# IOTKit_ch_open_V2.net
KiCad netlist of a schematic drawn in EAGLE
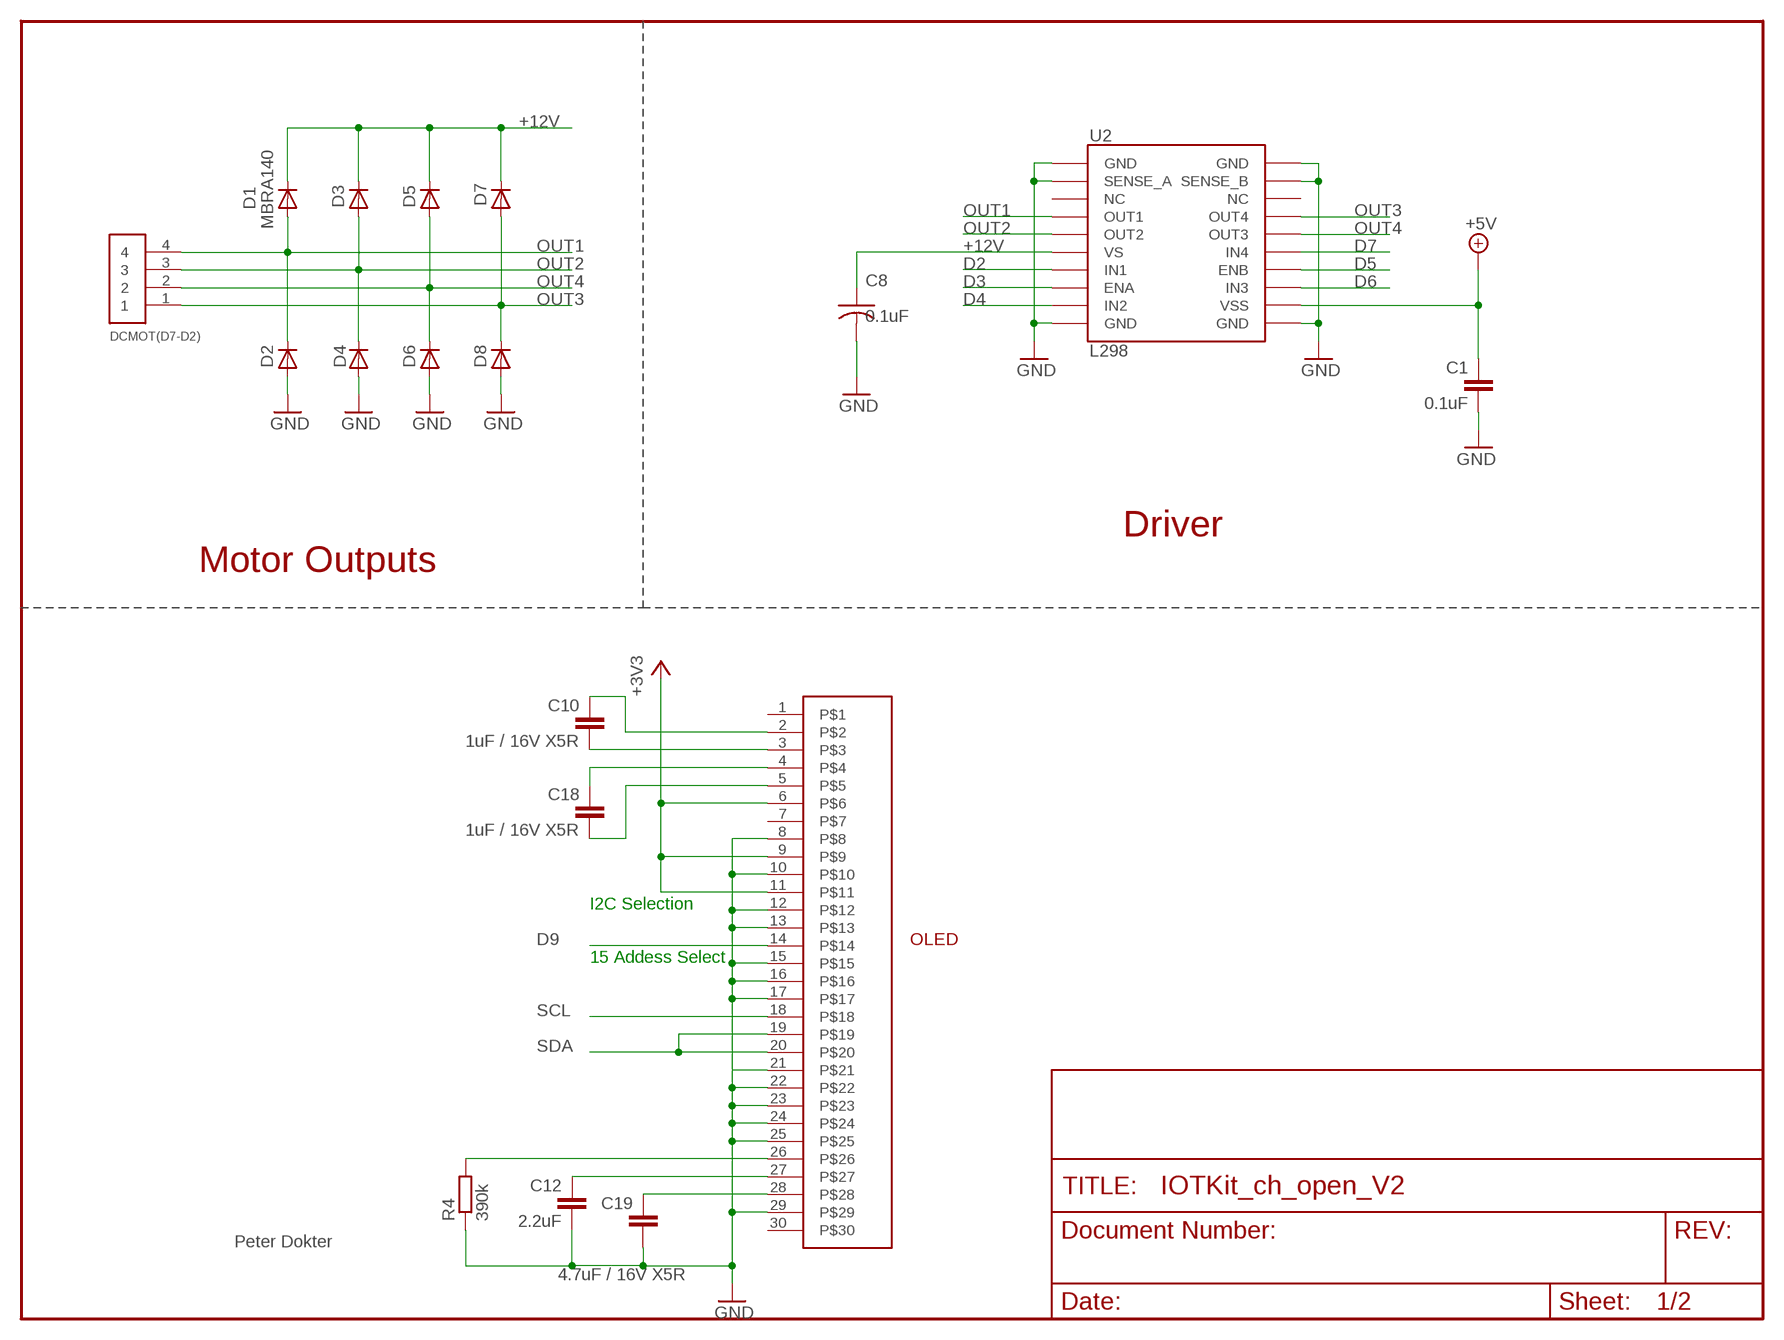
[diagram p0: schematic, sheet 1]
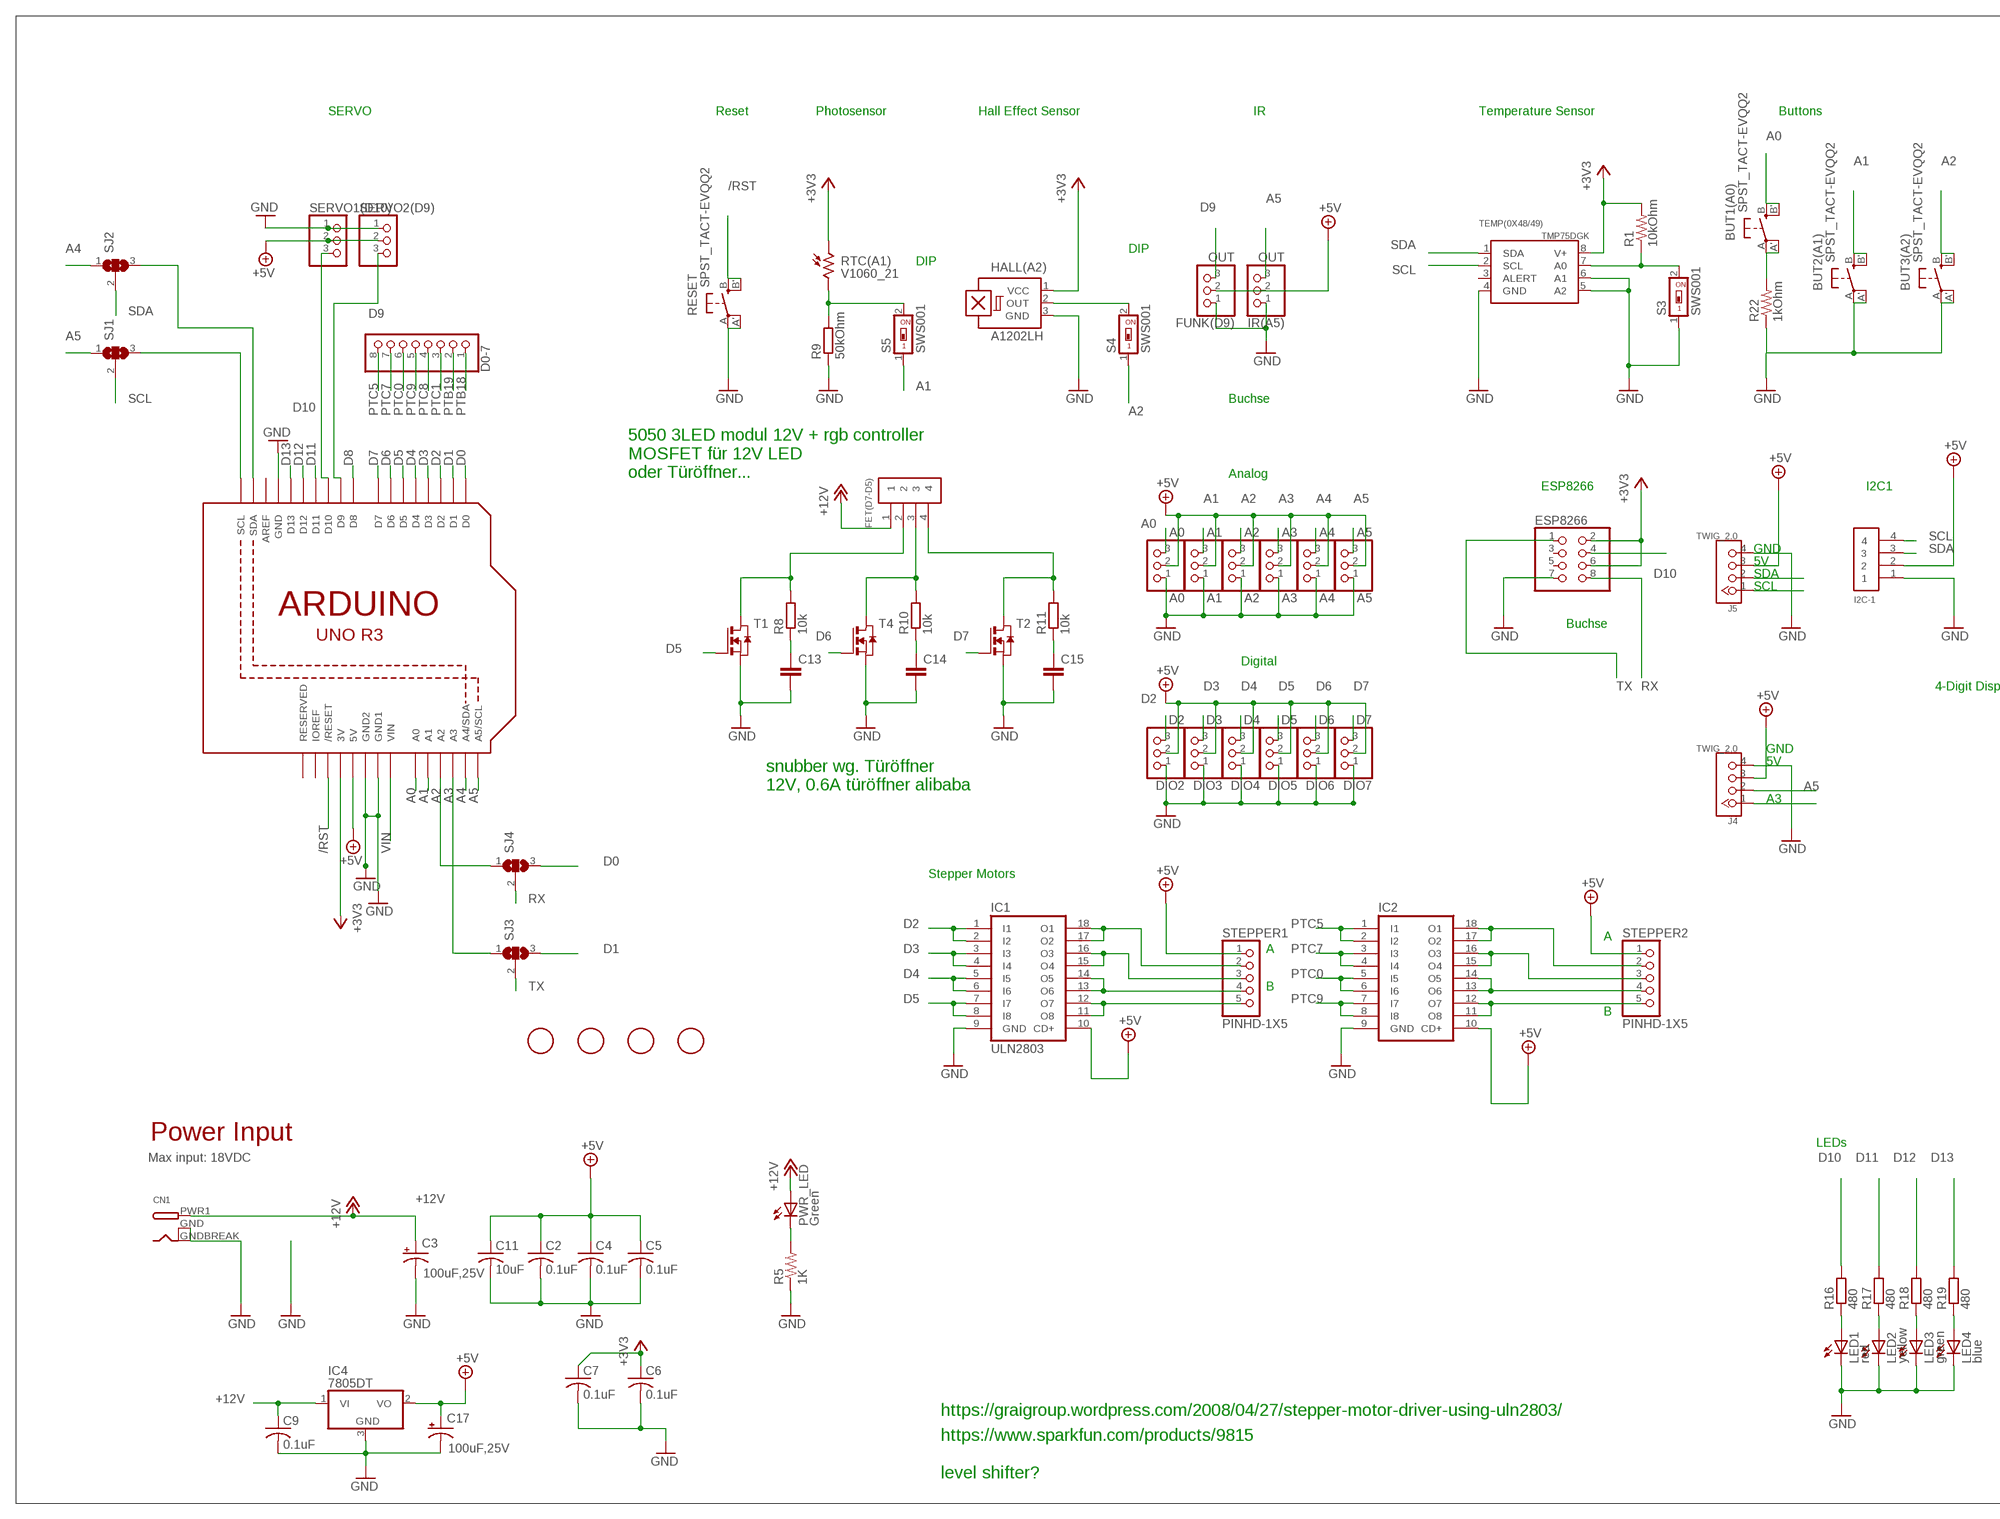
[diagram p1: schematic, sheet 2, part 1 of 2]
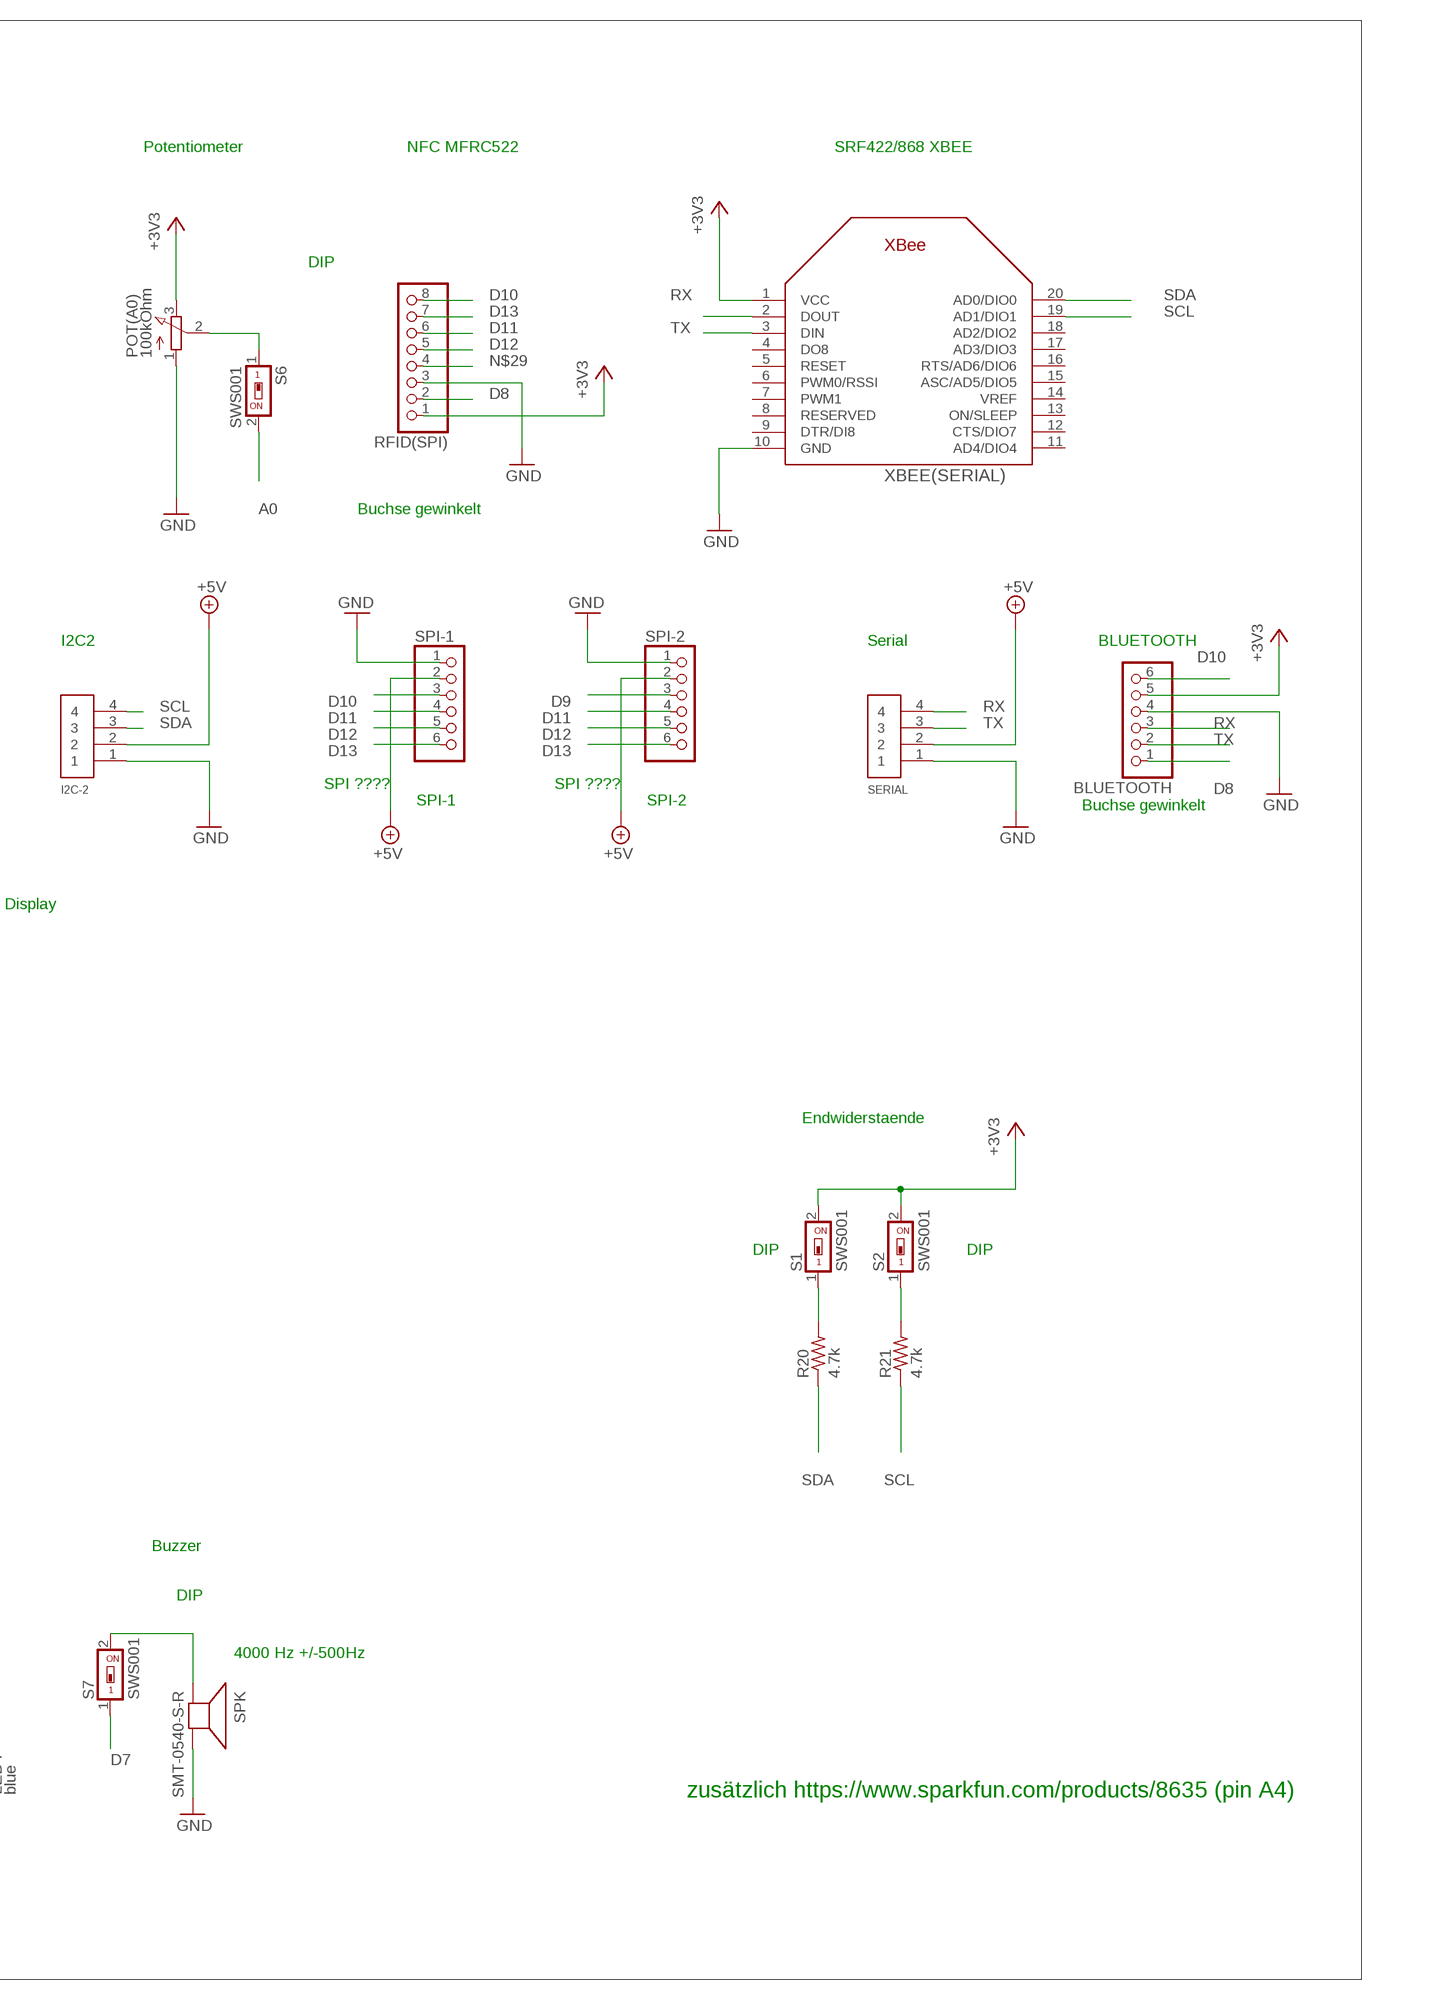
[diagram p2: schematic, sheet 2, part 2 of 2]

(export (version "E")
  (design (tool "Eeschema 10.0.6"))
  (components
    (comp (ref "A0")
      (value "A0")
      (footprint "eagle-import:1X03_LINE")
      (libsource (lib "eagle-import") (part "PINHD-1X3"))
    )
    (comp (ref "A1")
      (value "A1")
      (footprint "eagle-import:1X03_LINE")
      (libsource (lib "eagle-import") (part "PINHD-1X3"))
    )
    (comp (ref "A2")
      (value "A2")
      (footprint "eagle-import:1X03_LINE")
      (libsource (lib "eagle-import") (part "PINHD-1X3"))
    )
    (comp (ref "A3")
      (value "A3")
      (footprint "eagle-import:1X03_LINE")
      (libsource (lib "eagle-import") (part "PINHD-1X3"))
    )
    (comp (ref "A4")
      (value "A4")
      (footprint "eagle-import:1X03_LINE")
      (libsource (lib "eagle-import") (part "PINHD-1X3"))
    )
    (comp (ref "A5")
      (value "A5")
      (footprint "eagle-import:1X03_LINE")
      (libsource (lib "eagle-import") (part "PINHD-1X3"))
    )
    (comp (ref "BLUETOOTH")
      (value "PINHD-1X6B")
      (footprint "eagle-import:1X06-BIG")
      (libsource (lib "eagle-import") (part "PINHD-1X6B"))
    )
    (comp (ref "BUT1(A0)")
      (value "SPST_TACT-EVQQ2")
      (footprint "eagle-import:EVQ-Q2")
      (libsource (lib "eagle-import") (part "SPST_TACT-EVQQ2"))
    )
    (comp (ref "BUT2(A1)")
      (value "SPST_TACT-EVQQ2")
      (footprint "eagle-import:EVQ-Q2")
      (libsource (lib "eagle-import") (part "SPST_TACT-EVQQ2"))
    )
    (comp (ref "BUT3(A2)")
      (value "SPST_TACT-EVQQ2")
      (footprint "eagle-import:EVQ-Q2")
      (libsource (lib "eagle-import") (part "SPST_TACT-EVQQ2"))
    )
    (comp (ref "C2")
      (value "0.1uF")
      (footprint "eagle-import:C0603K")
      (libsource (lib "eagle-import") (part "C-USC0603K"))
    )
    (comp (ref "C3")
      (value "100uF,25V")
      (footprint "eagle-import:NIPPON_F80")
      (libsource (lib "eagle-import") (part "CAP_POLF80"))
    )
    (comp (ref "C4")
      (value "0.1uF")
      (footprint "eagle-import:C0603K")
      (libsource (lib "eagle-import") (part "C-USC0603K"))
    )
    (comp (ref "C5")
      (value "0.1uF")
      (footprint "eagle-import:C0603K")
      (libsource (lib "eagle-import") (part "C-USC0603K"))
    )
    (comp (ref "C6")
      (value "0.1uF")
      (footprint "eagle-import:C0603K")
      (libsource (lib "eagle-import") (part "C-USC0603K"))
    )
    (comp (ref "C7")
      (value "0.1uF")
      (footprint "eagle-import:C0603K")
      (libsource (lib "eagle-import") (part "C-USC0603K"))
    )
    (comp (ref "C9")
      (value "0.1uF")
      (footprint "eagle-import:C0805K")
      (libsource (lib "eagle-import") (part "C-USC0805K"))
    )
    (comp (ref "C11")
      (value "10uF")
      (footprint "eagle-import:C0805K")
      (libsource (lib "eagle-import") (part "C-USC0805K"))
    )
    (comp (ref "C13")
      (value "C-EUC0603")
      (footprint "eagle-import:C0603")
      (libsource (lib "eagle-import") (part "C-EUC0603"))
    )
    (comp (ref "C14")
      (value "C-EUC0603")
      (footprint "eagle-import:C0603")
      (libsource (lib "eagle-import") (part "C-EUC0603"))
    )
    (comp (ref "C15")
      (value "C-EUC0603")
      (footprint "eagle-import:C0603")
      (libsource (lib "eagle-import") (part "C-EUC0603"))
    )
    (comp (ref "C17")
      (value "100uF,25V")
      (footprint "eagle-import:NIPPON_F80")
      (libsource (lib "eagle-import") (part "CAP_POLF80"))
    )
    (comp (ref "CN1")
      (value "DCBARRELSMT")
      (footprint "eagle-import:DCJACK_2MM_SMT")
      (libsource (lib "eagle-import") (part "DCBARRELSMT"))
    )
    (comp (ref "D0-7")
      (value "PINHD-1X8CLEANBIG")
      (footprint "eagle-import:1X08-CLEANBIG")
      (libsource (lib "eagle-import") (part "PINHD-1X8CLEANBIG"))
    )
    (comp (ref "DIO2")
      (value "D2")
      (footprint "eagle-import:1X03_LINE")
      (libsource (lib "eagle-import") (part "PINHD-1X3"))
    )
    (comp (ref "DIO3")
      (value "D3")
      (footprint "eagle-import:1X03_LINE")
      (libsource (lib "eagle-import") (part "PINHD-1X3"))
    )
    (comp (ref "DIO4")
      (value "D4")
      (footprint "eagle-import:1X03_LINE")
      (libsource (lib "eagle-import") (part "PINHD-1X3"))
    )
    (comp (ref "DIO5")
      (value "D5")
      (footprint "eagle-import:1X03_LINE")
      (libsource (lib "eagle-import") (part "PINHD-1X3"))
    )
    (comp (ref "DIO6")
      (value "D6")
      (footprint "eagle-import:1X03_LINE")
      (libsource (lib "eagle-import") (part "PINHD-1X3"))
    )
    (comp (ref "DIO7")
      (value "D7")
      (footprint "eagle-import:1X03_LINE")
      (libsource (lib "eagle-import") (part "PINHD-1X3"))
    )
    (comp (ref "ESP8266")
      (value "PINHD-2X4")
      (footprint "eagle-import:2X04")
      (libsource (lib "eagle-import") (part "PINHD-2X4"))
    )
    (comp (ref "FET(D7-D5)")
      (value "1X4")
      (footprint "eagle-import:1X04_LINE")
      (libsource (lib "eagle-import") (part "1X4"))
    )
    (comp (ref "FUNK(D9)")
      (value "OUT")
      (footprint "eagle-import:1X03_LINE")
      (libsource (lib "eagle-import") (part "PINHD-1X3"))
    )
    (comp (ref "HALL(A2)")
      (value "A1202LH")
      (footprint "eagle-import:SOT23-W")
      (libsource (lib "eagle-import") (part "A12?LH02"))
    )
    (comp (ref "I2C-1")
      (value "1X4")
      (footprint "eagle-import:1X04_LINE")
      (libsource (lib "eagle-import") (part "1X4"))
    )
    (comp (ref "I2C-2")
      (value "1X4")
      (footprint "eagle-import:1X04_LINE")
      (libsource (lib "eagle-import") (part "1X4"))
    )
    (comp (ref "IC1")
      (value "ULN2803")
      (footprint "eagle-import:SO18W")
      (libsource (lib "eagle-import") (part "ULN2803ASO18W"))
    )
    (comp (ref "IC2")
      (value "ULN2803ASO18W")
      (footprint "eagle-import:SO18W")
      (libsource (lib "eagle-import") (part "ULN2803ASO18W"))
    )
    (comp (ref "IC4")
      (value "7805DT")
      (footprint "eagle-import:TO252")
      (libsource (lib "eagle-import") (part "78DT05"))
    )
    (comp (ref "IR(A5)")
      (value "OUT")
      (footprint "eagle-import:1X03_LINE")
      (libsource (lib "eagle-import") (part "PINHD-1X3"))
    )
    (comp (ref "J4")
      (value "TWIG_2.0")
      (footprint "eagle-import:2.0_1X4")
      (libsource (lib "eagle-import") (part "TWIG_2.0"))
    )
    (comp (ref "J5")
      (value "TWIG_2.0")
      (footprint "eagle-import:2.0_1X4")
      (libsource (lib "eagle-import") (part "TWIG_2.0"))
    )
    (comp (ref "LED1")
      (value "red")
      (footprint "eagle-import:CHIP-LED0603")
      (libsource (lib "eagle-import") (part "LEDCHIP-LED0603"))
    )
    (comp (ref "LED2")
      (value "yellow")
      (footprint "eagle-import:CHIP-LED0603")
      (libsource (lib "eagle-import") (part "LEDCHIP-LED0603"))
    )
    (comp (ref "LED3")
      (value "green")
      (footprint "eagle-import:CHIP-LED0603")
      (libsource (lib "eagle-import") (part "LEDCHIP-LED0603"))
    )
    (comp (ref "LED4")
      (value "blue")
      (footprint "eagle-import:CHIP-LED0603")
      (libsource (lib "eagle-import") (part "LEDCHIP-LED0603"))
    )
    (comp (ref "POT(A0)")
      (value "100kOhm")
      (footprint "eagle-import:EVUF")
      (libsource (lib "eagle-import") (part "EVUAF3"))
    )
    (comp (ref "PWR_LED")
      (value "Green")
      (footprint "eagle-import:CHIP-LED0805")
      (libsource (lib "eagle-import") (part "LEDCHIP-LED0805"))
    )
    (comp (ref "R1")
      (value "10kOhm")
      (footprint "eagle-import:R0805")
      (libsource (lib "eagle-import") (part "R-US_R0805"))
    )
    (comp (ref "R5")
      (value "1K")
      (footprint "eagle-import:R0805")
      (libsource (lib "eagle-import") (part "R-US_R0805"))
    )
    (comp (ref "R8")
      (value "10k")
      (footprint "eagle-import:R0805")
      (libsource (lib "eagle-import") (part "R-EU_R0805"))
    )
    (comp (ref "R9")
      (value "50kOhm")
      (footprint "eagle-import:R0603")
      (libsource (lib "eagle-import") (part "R-EU_R0603"))
    )
    (comp (ref "R10")
      (value "10k")
      (footprint "eagle-import:R0805")
      (libsource (lib "eagle-import") (part "R-EU_R0805"))
    )
    (comp (ref "R11")
      (value "10k")
      (footprint "eagle-import:R0805")
      (libsource (lib "eagle-import") (part "R-EU_R0805"))
    )
    (comp (ref "R16")
      (value "480")
      (footprint "eagle-import:R0603")
      (libsource (lib "eagle-import") (part "R-EU_R0603"))
    )
    (comp (ref "R17")
      (value "480")
      (footprint "eagle-import:R0603")
      (libsource (lib "eagle-import") (part "R-EU_R0603"))
    )
    (comp (ref "R18")
      (value "480")
      (footprint "eagle-import:R0603")
      (libsource (lib "eagle-import") (part "R-EU_R0603"))
    )
    (comp (ref "R19")
      (value "480")
      (footprint "eagle-import:R0603")
      (libsource (lib "eagle-import") (part "R-EU_R0603"))
    )
    (comp (ref "R20")
      (value "4.7k")
      (footprint "eagle-import:R0805")
      (libsource (lib "eagle-import") (part "R-US_R0805"))
    )
    (comp (ref "R21")
      (value "4.7k")
      (footprint "eagle-import:R0805")
      (libsource (lib "eagle-import") (part "R-US_R0805"))
    )
    (comp (ref "R22")
      (value "1kOhm")
      (footprint "eagle-import:R0805")
      (libsource (lib "eagle-import") (part "R-US_R0805"))
    )
    (comp (ref "RESET")
      (value "SPST_TACT-EVQQ2")
      (footprint "eagle-import:EVQ-Q2")
      (libsource (lib "eagle-import") (part "SPST_TACT-EVQQ2"))
    )
    (comp (ref "RFID(SPI)")
      (value "PINHD-1X8BIG")
      (footprint "eagle-import:1X08-BIG")
      (libsource (lib "eagle-import") (part "PINHD-1X8BIG"))
    )
    (comp (ref "RTC(A1)")
      (value "V1060_21")
      (footprint "eagle-import:TO-5_V10")
      (libsource (lib "eagle-import") (part "?1060V_21"))
    )
    (comp (ref "S1")
      (value "SWS001")
      (footprint "eagle-import:SMS-001")
      (libsource (lib "eagle-import") (part "SWS001"))
    )
    (comp (ref "S2")
      (value "SWS001")
      (footprint "eagle-import:SMS-001")
      (libsource (lib "eagle-import") (part "SWS001"))
    )
    (comp (ref "S3")
      (value "SWS001")
      (footprint "eagle-import:SMS-001")
      (libsource (lib "eagle-import") (part "SWS001"))
    )
    (comp (ref "S4")
      (value "SWS001")
      (footprint "eagle-import:SMS-001")
      (libsource (lib "eagle-import") (part "SWS001"))
    )
    (comp (ref "S5")
      (value "SWS001")
      (footprint "eagle-import:SMS-001")
      (libsource (lib "eagle-import") (part "SWS001"))
    )
    (comp (ref "S6")
      (value "SWS001")
      (footprint "eagle-import:SMS-001")
      (libsource (lib "eagle-import") (part "SWS001"))
    )
    (comp (ref "S7")
      (value "SWS001")
      (footprint "eagle-import:SMS-001")
      (libsource (lib "eagle-import") (part "SWS001"))
    )
    (comp (ref "SERIAL")
      (value "1X4")
      (footprint "eagle-import:1X04_LINE")
      (libsource (lib "eagle-import") (part "1X4"))
    )
    (comp (ref "SERVO1(D10)")
      (value "PINHD-1X3")
      (footprint "eagle-import:1X03")
      (libsource (lib "eagle-import") (part "adafruit_PINHD-1X3"))
    )
    (comp (ref "SERVO2(D9)")
      (value "PINHD-1X3")
      (footprint "eagle-import:1X03")
      (libsource (lib "eagle-import") (part "adafruit_PINHD-1X3"))
    )
    (comp (ref "SJ1")
      (value "SJ2W")
      (footprint "eagle-import:SJ_2")
      (libsource (lib "eagle-import") (part "SJ2W"))
    )
    (comp (ref "SJ2")
      (value "SJ2W")
      (footprint "eagle-import:SJ_2")
      (libsource (lib "eagle-import") (part "SJ2W"))
    )
    (comp (ref "SJ3")
      (value "SJ2W")
      (footprint "eagle-import:SJ_2")
      (libsource (lib "eagle-import") (part "SJ2W"))
    )
    (comp (ref "SJ4")
      (value "SJ2W")
      (footprint "eagle-import:SJ_2")
      (libsource (lib "eagle-import") (part "SJ2W"))
    )
    (comp (ref "SPI-1")
      (value "PINHD-1X6B")
      (footprint "eagle-import:1X06-BIG")
      (libsource (lib "eagle-import") (part "PINHD-1X6B"))
    )
    (comp (ref "SPI-2")
      (value "PINHD-1X6B")
      (footprint "eagle-import:1X06-BIG")
      (libsource (lib "eagle-import") (part "PINHD-1X6B"))
    )
    (comp (ref "SPK")
      (value "SMT-0540-S-R")
      (footprint "eagle-import:SMT-0540-S-R")
      (libsource (lib "eagle-import") (part "SMT-0540-S-R"))
    )
    (comp (ref "STEPPER1")
      (value "PINHD-1X5")
      (footprint "eagle-import:1X05")
      (libsource (lib "eagle-import") (part "PINHD-1X5"))
    )
    (comp (ref "STEPPER2")
      (value "PINHD-1X5")
      (footprint "eagle-import:1X05")
      (libsource (lib "eagle-import") (part "PINHD-1X5"))
    )
    (comp (ref "T1")
      (value "NMOSSOT223")
      (footprint "eagle-import:SOT223")
      (libsource (lib "eagle-import") (part "NMOSSOT223"))
    )
    (comp (ref "T2")
      (value "NMOSSOT223")
      (footprint "eagle-import:SOT223")
      (libsource (lib "eagle-import") (part "NMOSSOT223"))
    )
    (comp (ref "T4")
      (value "NMOSSOT223")
      (footprint "eagle-import:SOT223")
      (libsource (lib "eagle-import") (part "NMOSSOT223"))
    )
    (comp (ref "TEMP(0X48/49)")
      (value "TMP75DGK")
      (footprint "eagle-import:MSOP8")
      (libsource (lib "eagle-import") (part "TMP75DGK"))
    )
    (comp (ref "U$1")
      (value "FIDUCIAL")
      (footprint "eagle-import:FIDUCIAL_1MM")
      (libsource (lib "eagle-import") (part "FIDUCIAL"))
    )
    (comp (ref "U$2")
      (value "FIDUCIAL")
      (footprint "eagle-import:FIDUCIAL_1MM")
      (libsource (lib "eagle-import") (part "FIDUCIAL"))
    )
    (comp (ref "U$3")
      (value "FIDUCIAL")
      (footprint "eagle-import:FIDUCIAL_1MM")
      (libsource (lib "eagle-import") (part "FIDUCIAL"))
    )
    (comp (ref "U$5")
      (value "ARDUINOR3NONAME")
      (footprint "eagle-import:ARDUINOR2_ICSP_NODIM_NONAME")
      (libsource (lib "eagle-import") (part "ARDUINOR3NONAME"))
    )
    (comp (ref "U$6")
      (value "FIDUCIAL")
      (footprint "eagle-import:FIDUCIAL_1MM")
      (libsource (lib "eagle-import") (part "FIDUCIAL"))
    )
    (comp (ref "XBEE(SERIAL)")
      (value "XBEE")
      (footprint "eagle-import:XBEE")
      (libsource (lib "eagle-import") (part "XBEE"))
    )
    (comp (ref "C1")
      (value "0.1uF")
      (footprint "eagle-import:0402-CAP")
      (libsource (lib "eagle-import") (part "CAP0402-CAP"))
    )
    (comp (ref "C8")
      (value "0.1uF")
      (footprint "eagle-import:C0603K")
      (libsource (lib "eagle-import") (part "C-USC0603K"))
    )
    (comp (ref "C10")
      (value "1uF / 16V X5R")
      (footprint "eagle-import:0603-CAP")
      (libsource (lib "eagle-import") (part "CAP0603-CAP"))
    )
    (comp (ref "C12")
      (value "2.2uF")
      (footprint "eagle-import:0603-CAP")
      (libsource (lib "eagle-import") (part "CAP0603-CAP"))
    )
    (comp (ref "C18")
      (value "1uF / 16V X5R")
      (footprint "eagle-import:0603-CAP")
      (libsource (lib "eagle-import") (part "CAP0603-CAP"))
    )
    (comp (ref "C19")
      (value "4.7uF / 16V X5R")
      (footprint "eagle-import:0603-CAP")
      (libsource (lib "eagle-import") (part "CAP0603-CAP"))
    )
    (comp (ref "D1")
      (value "MBRA140")
      (footprint "eagle-import:SMA-DIODE")
      (libsource (lib "eagle-import") (part "DIODESMA"))
    )
    (comp (ref "D2")
      (value "MBRA140")
      (footprint "eagle-import:SMA-DIODE")
      (libsource (lib "eagle-import") (part "DIODESMA"))
    )
    (comp (ref "D3")
      (value "MBRA140")
      (footprint "eagle-import:SMA-DIODE")
      (libsource (lib "eagle-import") (part "DIODESMA"))
    )
    (comp (ref "D4")
      (value "MBRA140")
      (footprint "eagle-import:SMA-DIODE")
      (libsource (lib "eagle-import") (part "DIODESMA"))
    )
    (comp (ref "D5")
      (value "MBRA140")
      (footprint "eagle-import:SMA-DIODE")
      (libsource (lib "eagle-import") (part "DIODESMA"))
    )
    (comp (ref "D6")
      (value "MBRA140")
      (footprint "eagle-import:SMA-DIODE")
      (libsource (lib "eagle-import") (part "DIODESMA"))
    )
    (comp (ref "D7")
      (value "MBRA140")
      (footprint "eagle-import:SMA-DIODE")
      (libsource (lib "eagle-import") (part "DIODESMA"))
    )
    (comp (ref "D8")
      (value "MBRA140")
      (footprint "eagle-import:SMA-DIODE")
      (libsource (lib "eagle-import") (part "DIODESMA"))
    )
    (comp (ref "DCMOT(D7-D2)")
      (value "1X4")
      (footprint "eagle-import:1X04_LINE")
      (libsource (lib "eagle-import") (part "1X4"))
    )
    (comp (ref "R4")
      (value "390k")
      (footprint "eagle-import:R0603")
      (libsource (lib "eagle-import") (part "R-EU_R0603"))
    )
    (comp (ref "U$4")
      (value "OLED_096_1")
      (footprint "eagle-import:OLED_096_1")
      (libsource (lib "eagle-import") (part "OLED_096_1"))
    )
    (comp (ref "U2")
      (value "L298")
      (footprint "eagle-import:POWERSO20")
      (libsource (lib "eagle-import") (part "L298_BRIDGE_DRIVER"))
    )
  )
  (nets
    (net (code "1") (name "+3V3") (class "Default")
      (node (ref "BLUETOOTH") (pin "5") (pinfunction "5_5") (pintype "passive"))
      (node (ref "C6") (pin "1") (pinfunction "1_1") (pintype "passive"))
      (node (ref "C7") (pin "1") (pinfunction "1_1") (pintype "passive"))
      (node (ref "ESP8266") (pin "2") (pinfunction "2_2") (pintype "passive"))
      (node (ref "ESP8266") (pin "6") (pinfunction "6_6") (pintype "passive"))
      (node (ref "HALL(A2)") (pin "1") (pinfunction "VCC_1") (pintype "power_in"))
      (node (ref "POT(A0)") (pin "3") (pinfunction "E_3") (pintype "passive"))
      (node (ref "R1") (pin "2") (pinfunction "2_2") (pintype "passive"))
      (node (ref "RFID(SPI)") (pin "1") (pinfunction "1_1") (pintype "passive"))
      (node (ref "RTC(A1)") (pin "1") (pinfunction "1_1") (pintype "passive"))
      (node (ref "S1") (pin "2") (pinfunction "2_2") (pintype "passive"))
      (node (ref "S2") (pin "2") (pinfunction "2_2") (pintype "passive"))
      (node (ref "TEMP(0X48/49)") (pin "8") (pinfunction "V+_8") (pintype "bidirectional"))
      (node (ref "U$4") (pin "11") (pinfunction "P$11_11") (pintype "bidirectional"))
      (node (ref "U$4") (pin "6") (pinfunction "P$6_6") (pintype "bidirectional"))
      (node (ref "U$4") (pin "9") (pinfunction "P$9_9") (pintype "bidirectional"))
      (node (ref "U$5") (pin "3V") (pinfunction "3V_3V") (pintype "power_in"))
      (node (ref "XBEE(SERIAL)") (pin "1") (pinfunction "VCC_1") (pintype "power_in"))
    )
    (net (code "2") (name "+5V") (class "Default")
      (node (ref "A0") (pin "2") (pinfunction "2_2") (pintype "passive"))
      (node (ref "A1") (pin "2") (pinfunction "2_2") (pintype "passive"))
      (node (ref "A2") (pin "2") (pinfunction "2_2") (pintype "passive"))
      (node (ref "A3") (pin "2") (pinfunction "2_2") (pintype "passive"))
      (node (ref "A4") (pin "2") (pinfunction "2_2") (pintype "passive"))
      (node (ref "A5") (pin "2") (pinfunction "2_2") (pintype "passive"))
      (node (ref "C1") (pin "1") (pinfunction "1_1") (pintype "passive"))
      (node (ref "C11") (pin "1") (pinfunction "1_1") (pintype "passive"))
      (node (ref "C17") (pin "+") (pinfunction "+_+") (pintype "passive"))
      (node (ref "C2") (pin "1") (pinfunction "1_1") (pintype "passive"))
      (node (ref "C4") (pin "1") (pinfunction "1_1") (pintype "passive"))
      (node (ref "C5") (pin "1") (pinfunction "1_1") (pintype "passive"))
      (node (ref "DIO2") (pin "2") (pinfunction "2_2") (pintype "passive"))
      (node (ref "DIO3") (pin "2") (pinfunction "2_2") (pintype "passive"))
      (node (ref "DIO4") (pin "2") (pinfunction "2_2") (pintype "passive"))
      (node (ref "DIO5") (pin "2") (pinfunction "2_2") (pintype "passive"))
      (node (ref "DIO6") (pin "2") (pinfunction "2_2") (pintype "passive"))
      (node (ref "DIO7") (pin "2") (pinfunction "2_2") (pintype "passive"))
      (node (ref "FUNK(D9)") (pin "2") (pinfunction "2_2") (pintype "passive"))
      (node (ref "I2C-1") (pin "2") (pinfunction "2_2") (pintype "bidirectional"))
      (node (ref "I2C-2") (pin "2") (pinfunction "2_2") (pintype "bidirectional"))
      (node (ref "IC1") (pin "10") (pinfunction "CD+_10") (pintype "passive"))
      (node (ref "IC2") (pin "10") (pinfunction "CD+_10") (pintype "passive"))
      (node (ref "IC4") (pin "2") (pinfunction "VO_2") (pintype "passive"))
      (node (ref "IR(A5)") (pin "2") (pinfunction "2_2") (pintype "passive"))
      (node (ref "J4") (pin "3") (pinfunction "3_3") (pintype "bidirectional"))
      (node (ref "J5") (pin "3") (pinfunction "3_3") (pintype "bidirectional"))
      (node (ref "SERIAL") (pin "2") (pinfunction "2_2") (pintype "bidirectional"))
      (node (ref "SERVO1(D10)") (pin "2") (pinfunction "2_2") (pintype "passive"))
      (node (ref "SERVO2(D9)") (pin "2") (pinfunction "2_2") (pintype "passive"))
      (node (ref "SPI-1") (pin "2") (pinfunction "2_2") (pintype "passive"))
      (node (ref "SPI-2") (pin "2") (pinfunction "2_2") (pintype "passive"))
      (node (ref "STEPPER1") (pin "1") (pinfunction "1_1") (pintype "passive"))
      (node (ref "STEPPER2") (pin "1") (pinfunction "1_1") (pintype "passive"))
      (node (ref "U$5") (pin "5V") (pinfunction "5V_5V") (pintype "power_in"))
      (node (ref "U2") (pin "P$12") (pinfunction "VSS_P$12") (pintype "bidirectional"))
    )
    (net (code "3") (name "+12V") (class "Default")
      (node (ref "C3") (pin "+") (pinfunction "+_+") (pintype "passive"))
      (node (ref "C8") (pin "1") (pinfunction "1_1") (pintype "passive"))
      (node (ref "C9") (pin "1") (pinfunction "1_1") (pintype "passive"))
      (node (ref "CN1") (pin "PWR1") (pinfunction "PWR_PWR1") (pintype "power_in"))
      (node (ref "D1") (pin "C") (pinfunction "C_C") (pintype "passive"))
      (node (ref "D3") (pin "C") (pinfunction "C_C") (pintype "passive"))
      (node (ref "D5") (pin "C") (pinfunction "C_C") (pintype "passive"))
      (node (ref "D7") (pin "C") (pinfunction "C_C") (pintype "passive"))
      (node (ref "FET(D7-D5)") (pin "1") (pinfunction "1_1") (pintype "bidirectional"))
      (node (ref "IC4") (pin "1") (pinfunction "VI_1") (pintype "input"))
      (node (ref "PWR_LED") (pin "A") (pinfunction "A_A") (pintype "passive"))
      (node (ref "U2") (pin "P$6") (pinfunction "VS_P$6") (pintype "bidirectional"))
    )
    (net (code "4") (name "A0") (class "Default")
      (node (ref "A0") (pin "3") (pinfunction "3_3") (pintype "passive"))
      (node (ref "BUT1(A0)") (pin "B") (pinfunction "S_B") (pintype "passive"))
      (node (ref "BUT1(A0)") (pin "B'") (pinfunction "S1_B'") (pintype "passive"))
      (node (ref "S6") (pin "2") (pinfunction "2_2") (pintype "passive"))
      (node (ref "U$5") (pin "A0") (pinfunction "A0_A0") (pintype "bidirectional"))
    )
    (net (code "5") (name "A1") (class "Default")
      (node (ref "A1") (pin "3") (pinfunction "3_3") (pintype "passive"))
      (node (ref "BUT2(A1)") (pin "B") (pinfunction "S_B") (pintype "passive"))
      (node (ref "BUT2(A1)") (pin "B'") (pinfunction "S1_B'") (pintype "passive"))
      (node (ref "S5") (pin "1") (pinfunction "1_1") (pintype "passive"))
      (node (ref "U$5") (pin "A1") (pinfunction "A1_A1") (pintype "bidirectional"))
    )
    (net (code "6") (name "A2") (class "Default")
      (node (ref "A2") (pin "3") (pinfunction "3_3") (pintype "passive"))
      (node (ref "BUT3(A2)") (pin "B") (pinfunction "S_B") (pintype "passive"))
      (node (ref "BUT3(A2)") (pin "B'") (pinfunction "S1_B'") (pintype "passive"))
      (node (ref "S4") (pin "1") (pinfunction "1_1") (pintype "passive"))
      (node (ref "SJ4") (pin "1") (pinfunction "1_1") (pintype "passive"))
      (node (ref "U$5") (pin "A2") (pinfunction "A2_A2") (pintype "bidirectional"))
    )
    (net (code "7") (name "A3") (class "Default")
      (node (ref "A3") (pin "3") (pinfunction "3_3") (pintype "passive"))
      (node (ref "J4") (pin "1") (pinfunction "1_1") (pintype "bidirectional"))
      (node (ref "SJ3") (pin "1") (pinfunction "1_1") (pintype "passive"))
      (node (ref "U$5") (pin "A3") (pinfunction "A3_A3") (pintype "bidirectional"))
    )
    (net (code "8") (name "A4") (class "Default")
      (node (ref "A4") (pin "3") (pinfunction "3_3") (pintype "passive"))
      (node (ref "SJ2") (pin "1") (pinfunction "1_1") (pintype "passive"))
      (node (ref "U$5") (pin "A4") (pinfunction "A4/SDA_A4") (pintype "bidirectional"))
    )
    (net (code "9") (name "A5") (class "Default")
      (node (ref "A5") (pin "3") (pinfunction "3_3") (pintype "passive"))
      (node (ref "IR(A5)") (pin "3") (pinfunction "3_3") (pintype "passive"))
      (node (ref "J4") (pin "2") (pinfunction "2_2") (pintype "bidirectional"))
      (node (ref "SJ1") (pin "1") (pinfunction "1_1") (pintype "passive"))
      (node (ref "U$5") (pin "A5") (pinfunction "A5/SCL_A5") (pintype "bidirectional"))
    )
    (net (code "10") (name "D0") (class "Default")
      (node (ref "SJ4") (pin "3") (pinfunction "3_3") (pintype "passive"))
      (node (ref "U$5") (pin "D0") (pinfunction "D0_D0") (pintype "bidirectional"))
    )
    (net (code "11") (name "D1") (class "Default")
      (node (ref "SJ3") (pin "3") (pinfunction "3_3") (pintype "passive"))
      (node (ref "U$5") (pin "D1") (pinfunction "D1_D1") (pintype "bidirectional"))
    )
    (net (code "12") (name "D2") (class "Default")
      (node (ref "DIO2") (pin "3") (pinfunction "3_3") (pintype "passive"))
      (node (ref "IC1") (pin "1") (pinfunction "I1_1") (pintype "input"))
      (node (ref "IC1") (pin "2") (pinfunction "I2_2") (pintype "input"))
      (node (ref "U$5") (pin "D2") (pinfunction "D2_D2") (pintype "bidirectional"))
      (node (ref "U2") (pin "P$7") (pinfunction "IN1_P$7") (pintype "bidirectional"))
    )
    (net (code "13") (name "D3") (class "Default")
      (node (ref "DIO3") (pin "3") (pinfunction "3_3") (pintype "passive"))
      (node (ref "IC1") (pin "3") (pinfunction "I3_3") (pintype "input"))
      (node (ref "IC1") (pin "4") (pinfunction "I4_4") (pintype "input"))
      (node (ref "U$5") (pin "D3") (pinfunction "D3_D3") (pintype "bidirectional"))
      (node (ref "U2") (pin "P$8") (pinfunction "ENA_P$8") (pintype "bidirectional"))
    )
    (net (code "14") (name "D4") (class "Default")
      (node (ref "DIO4") (pin "3") (pinfunction "3_3") (pintype "passive"))
      (node (ref "IC1") (pin "5") (pinfunction "I5_5") (pintype "input"))
      (node (ref "IC1") (pin "6") (pinfunction "I6_6") (pintype "input"))
      (node (ref "U$5") (pin "D4") (pinfunction "D4_D4") (pintype "bidirectional"))
      (node (ref "U2") (pin "P$9") (pinfunction "IN2_P$9") (pintype "bidirectional"))
    )
    (net (code "15") (name "D5") (class "Default")
      (node (ref "DIO5") (pin "3") (pinfunction "3_3") (pintype "passive"))
      (node (ref "IC1") (pin "7") (pinfunction "I7_7") (pintype "input"))
      (node (ref "IC1") (pin "8") (pinfunction "I8_8") (pintype "input"))
      (node (ref "T1") (pin "1") (pinfunction "G_1") (pintype "passive"))
      (node (ref "U$5") (pin "D5") (pinfunction "D5_D5") (pintype "bidirectional"))
      (node (ref "U2") (pin "P$14") (pinfunction "ENB_P$14") (pintype "bidirectional"))
    )
    (net (code "16") (name "D6") (class "Default")
      (node (ref "DIO6") (pin "3") (pinfunction "3_3") (pintype "passive"))
      (node (ref "T4") (pin "1") (pinfunction "G_1") (pintype "passive"))
      (node (ref "U$5") (pin "D6") (pinfunction "D6_D6") (pintype "bidirectional"))
      (node (ref "U2") (pin "P$13") (pinfunction "IN3_P$13") (pintype "bidirectional"))
    )
    (net (code "17") (name "D7") (class "Default")
      (node (ref "DIO7") (pin "3") (pinfunction "3_3") (pintype "passive"))
      (node (ref "S7") (pin "1") (pinfunction "1_1") (pintype "passive"))
      (node (ref "T2") (pin "1") (pinfunction "G_1") (pintype "passive"))
      (node (ref "U$5") (pin "D7") (pinfunction "D7_D7") (pintype "bidirectional"))
      (node (ref "U2") (pin "P$15") (pinfunction "IN4_P$15") (pintype "bidirectional"))
    )
    (net (code "18") (name "D8") (class "Default")
      (node (ref "BLUETOOTH") (pin "1") (pinfunction "1_1") (pintype "passive"))
      (node (ref "RFID(SPI)") (pin "2") (pinfunction "2_2") (pintype "passive"))
      (node (ref "U$5") (pin "D8") (pinfunction "D8_D8") (pintype "bidirectional"))
    )
    (net (code "19") (name "D9") (class "Default")
      (node (ref "FUNK(D9)") (pin "3") (pinfunction "3_3") (pintype "passive"))
      (node (ref "SERVO2(D9)") (pin "3") (pinfunction "3_3") (pintype "passive"))
      (node (ref "SPI-2") (pin "3") (pinfunction "3_3") (pintype "passive"))
      (node (ref "U$4") (pin "14") (pinfunction "P$14_14") (pintype "bidirectional"))
      (node (ref "U$5") (pin "D9") (pinfunction "D9_D9") (pintype "bidirectional"))
    )
    (net (code "20") (name "D10") (class "Default")
      (node (ref "BLUETOOTH") (pin "6") (pinfunction "6_6") (pintype "passive"))
      (node (ref "ESP8266") (pin "4") (pinfunction "4_4") (pintype "passive"))
      (node (ref "R16") (pin "2") (pinfunction "2_2") (pintype "passive"))
      (node (ref "RFID(SPI)") (pin "8") (pinfunction "8_8") (pintype "passive"))
      (node (ref "SERVO1(D10)") (pin "3") (pinfunction "3_3") (pintype "passive"))
      (node (ref "SPI-1") (pin "3") (pinfunction "3_3") (pintype "passive"))
      (node (ref "U$5") (pin "D10") (pinfunction "D10_D10") (pintype "bidirectional"))
    )
    (net (code "21") (name "D11") (class "Default")
      (node (ref "R17") (pin "2") (pinfunction "2_2") (pintype "passive"))
      (node (ref "RFID(SPI)") (pin "6") (pinfunction "6_6") (pintype "passive"))
      (node (ref "SPI-1") (pin "4") (pinfunction "4_4") (pintype "passive"))
      (node (ref "SPI-2") (pin "4") (pinfunction "4_4") (pintype "passive"))
      (node (ref "U$5") (pin "D11") (pinfunction "D11_D11") (pintype "bidirectional"))
    )
    (net (code "22") (name "D12") (class "Default")
      (node (ref "R18") (pin "2") (pinfunction "2_2") (pintype "passive"))
      (node (ref "RFID(SPI)") (pin "5") (pinfunction "5_5") (pintype "passive"))
      (node (ref "SPI-1") (pin "5") (pinfunction "5_5") (pintype "passive"))
      (node (ref "SPI-2") (pin "5") (pinfunction "5_5") (pintype "passive"))
      (node (ref "U$5") (pin "D12") (pinfunction "D12_D12") (pintype "bidirectional"))
    )
    (net (code "23") (name "D13") (class "Default")
      (node (ref "R19") (pin "2") (pinfunction "2_2") (pintype "passive"))
      (node (ref "RFID(SPI)") (pin "7") (pinfunction "7_7") (pintype "passive"))
      (node (ref "SPI-1") (pin "6") (pinfunction "6_6") (pintype "passive"))
      (node (ref "SPI-2") (pin "6") (pinfunction "6_6") (pintype "passive"))
      (node (ref "U$5") (pin "D13") (pinfunction "D13_D13") (pintype "bidirectional"))
    )
    (net (code "24") (name "GND") (class "Default")
      (node (ref "A0") (pin "1") (pinfunction "1_1") (pintype "passive"))
      (node (ref "A1") (pin "1") (pinfunction "1_1") (pintype "passive"))
      (node (ref "A2") (pin "1") (pinfunction "1_1") (pintype "passive"))
      (node (ref "A3") (pin "1") (pinfunction "1_1") (pintype "passive"))
      (node (ref "A4") (pin "1") (pinfunction "1_1") (pintype "passive"))
      (node (ref "A5") (pin "1") (pinfunction "1_1") (pintype "passive"))
      (node (ref "BLUETOOTH") (pin "4") (pinfunction "4_4") (pintype "passive"))
      (node (ref "BUT2(A1)") (pin "A") (pinfunction "P_A") (pintype "passive"))
      (node (ref "BUT2(A1)") (pin "A'") (pinfunction "P1_A'") (pintype "passive"))
      (node (ref "BUT3(A2)") (pin "A") (pinfunction "P_A") (pintype "passive"))
      (node (ref "BUT3(A2)") (pin "A'") (pinfunction "P1_A'") (pintype "passive"))
      (node (ref "C1") (pin "2") (pinfunction "2_2") (pintype "passive"))
      (node (ref "C11") (pin "2") (pinfunction "2_2") (pintype "passive"))
      (node (ref "C12") (pin "2") (pinfunction "2_2") (pintype "passive"))
      (node (ref "C13") (pin "2") (pinfunction "2_2") (pintype "passive"))
      (node (ref "C14") (pin "2") (pinfunction "2_2") (pintype "passive"))
      (node (ref "C15") (pin "2") (pinfunction "2_2") (pintype "passive"))
      (node (ref "C17") (pin "-") (pinfunction "-_-") (pintype "passive"))
      (node (ref "C19") (pin "2") (pinfunction "2_2") (pintype "passive"))
      (node (ref "C2") (pin "2") (pinfunction "2_2") (pintype "passive"))
      (node (ref "C3") (pin "-") (pinfunction "-_-") (pintype "passive"))
      (node (ref "C4") (pin "2") (pinfunction "2_2") (pintype "passive"))
      (node (ref "C5") (pin "2") (pinfunction "2_2") (pintype "passive"))
      (node (ref "C6") (pin "2") (pinfunction "2_2") (pintype "passive"))
      (node (ref "C7") (pin "2") (pinfunction "2_2") (pintype "passive"))
      (node (ref "C8") (pin "2") (pinfunction "2_2") (pintype "passive"))
      (node (ref "C9") (pin "2") (pinfunction "2_2") (pintype "passive"))
      (node (ref "CN1") (pin "GND") (pinfunction "GNDBREAK_GND") (pintype "power_in"))
      (node (ref "CN1") (pin "GNDBREAK") (pinfunction "GND_GNDBREAK") (pintype "power_in"))
      (node (ref "D2") (pin "A") (pinfunction "A_A") (pintype "passive"))
      (node (ref "D4") (pin "A") (pinfunction "A_A") (pintype "passive"))
      (node (ref "D6") (pin "A") (pinfunction "A_A") (pintype "passive"))
      (node (ref "D8") (pin "A") (pinfunction "A_A") (pintype "passive"))
      (node (ref "DIO2") (pin "1") (pinfunction "1_1") (pintype "passive"))
      (node (ref "DIO3") (pin "1") (pinfunction "1_1") (pintype "passive"))
      (node (ref "DIO4") (pin "1") (pinfunction "1_1") (pintype "passive"))
      (node (ref "DIO5") (pin "1") (pinfunction "1_1") (pintype "passive"))
      (node (ref "DIO6") (pin "1") (pinfunction "1_1") (pintype "passive"))
      (node (ref "DIO7") (pin "1") (pinfunction "1_1") (pintype "passive"))
      (node (ref "ESP8266") (pin "7") (pinfunction "7_7") (pintype "passive"))
      (node (ref "FUNK(D9)") (pin "1") (pinfunction "1_1") (pintype "passive"))
      (node (ref "HALL(A2)") (pin "3") (pinfunction "GND_3") (pintype "power_in"))
      (node (ref "I2C-1") (pin "1") (pinfunction "1_1") (pintype "bidirectional"))
      (node (ref "I2C-2") (pin "1") (pinfunction "1_1") (pintype "bidirectional"))
      (node (ref "IC1") (pin "9") (pinfunction "GND_9") (pintype "power_in"))
      (node (ref "IC2") (pin "9") (pinfunction "GND_9") (pintype "power_in"))
      (node (ref "IC4") (pin "3") (pinfunction "GND_3") (pintype "passive"))
      (node (ref "IR(A5)") (pin "1") (pinfunction "1_1") (pintype "passive"))
      (node (ref "J4") (pin "4") (pinfunction "4_4") (pintype "bidirectional"))
      (node (ref "J5") (pin "4") (pinfunction "4_4") (pintype "bidirectional"))
      (node (ref "LED1") (pin "C") (pinfunction "C_C") (pintype "passive"))
      (node (ref "LED2") (pin "C") (pinfunction "C_C") (pintype "passive"))
      (node (ref "LED3") (pin "C") (pinfunction "C_C") (pintype "passive"))
      (node (ref "LED4") (pin "C") (pinfunction "C_C") (pintype "passive"))
      (node (ref "POT(A0)") (pin "1") (pinfunction "A_1") (pintype "passive"))
      (node (ref "R22") (pin "1") (pinfunction "1_1") (pintype "passive"))
      (node (ref "R4") (pin "1") (pinfunction "1_1") (pintype "passive"))
      (node (ref "R5") (pin "1") (pinfunction "1_1") (pintype "passive"))
      (node (ref "R9") (pin "1") (pinfunction "1_1") (pintype "passive"))
      (node (ref "RESET") (pin "A") (pinfunction "P_A") (pintype "passive"))
      (node (ref "RESET") (pin "A'") (pinfunction "P1_A'") (pintype "passive"))
      (node (ref "RFID(SPI)") (pin "3") (pinfunction "3_3") (pintype "passive"))
      (node (ref "S3") (pin "1") (pinfunction "1_1") (pintype "passive"))
      (node (ref "SERIAL") (pin "1") (pinfunction "1_1") (pintype "bidirectional"))
      (node (ref "SERVO1(D10)") (pin "1") (pinfunction "1_1") (pintype "passive"))
      (node (ref "SERVO2(D9)") (pin "1") (pinfunction "1_1") (pintype "passive"))
      (node (ref "SPI-1") (pin "1") (pinfunction "1_1") (pintype "passive"))
      (node (ref "SPI-2") (pin "1") (pinfunction "1_1") (pintype "passive"))
      (node (ref "SPK") (pin "+") (pinfunction "-_+") (pintype "passive"))
      (node (ref "T1") (pin "3") (pinfunction "S_3") (pintype "passive"))
      (node (ref "T2") (pin "3") (pinfunction "S_3") (pintype "passive"))
      (node (ref "T4") (pin "3") (pinfunction "S_3") (pintype "passive"))
      (node (ref "TEMP(0X48/49)") (pin "4") (pinfunction "GND_4") (pintype "bidirectional"))
      (node (ref "TEMP(0X48/49)") (pin "5") (pinfunction "A2_5") (pintype "bidirectional"))
      (node (ref "TEMP(0X48/49)") (pin "6") (pinfunction "A1_6") (pintype "bidirectional"))
      (node (ref "U$4") (pin "10") (pinfunction "P$10_10") (pintype "bidirectional"))
      (node (ref "U$4") (pin "12") (pinfunction "P$12_12") (pintype "bidirectional"))
      (node (ref "U$4") (pin "13") (pinfunction "P$13_13") (pintype "bidirectional"))
      (node (ref "U$4") (pin "15") (pinfunction "P$15_15") (pintype "bidirectional"))
      (node (ref "U$4") (pin "16") (pinfunction "P$16_16") (pintype "bidirectional"))
      (node (ref "U$4") (pin "17") (pinfunction "P$17_17") (pintype "bidirectional"))
      (node (ref "U$4") (pin "21") (pinfunction "P$21_21") (pintype "bidirectional"))
      (node (ref "U$4") (pin "22") (pinfunction "P$22_22") (pintype "bidirectional"))
      (node (ref "U$4") (pin "23") (pinfunction "P$23_23") (pintype "bidirectional"))
      (node (ref "U$4") (pin "24") (pinfunction "P$24_24") (pintype "bidirectional"))
      (node (ref "U$4") (pin "25") (pinfunction "P$25_25") (pintype "bidirectional"))
      (node (ref "U$4") (pin "29") (pinfunction "P$29_29") (pintype "bidirectional"))
      (node (ref "U$4") (pin "8") (pinfunction "P$8_8") (pintype "bidirectional"))
      (node (ref "U$5") (pin "GND") (pinfunction "GND_GND") (pintype "power_in"))
      (node (ref "U$5") (pin "GND@1") (pinfunction "GND1_GND@1") (pintype "power_in"))
      (node (ref "U$5") (pin "GND@2") (pinfunction "GND2_GND@2") (pintype "power_in"))
      (node (ref "U2") (pin "P$1") (pinfunction "GND_P$1") (pintype "bidirectional"))
      (node (ref "U2") (pin "P$10") (pinfunction "GND_P$10") (pintype "bidirectional"))
      (node (ref "U2") (pin "P$11") (pinfunction "GND_P$11") (pintype "bidirectional"))
      (node (ref "U2") (pin "P$19") (pinfunction "SENSE_B_P$19") (pintype "bidirectional"))
      (node (ref "U2") (pin "P$2") (pinfunction "SENSE_A_P$2") (pintype "bidirectional"))
      (node (ref "U2") (pin "P$20") (pinfunction "GND_P$20") (pintype "bidirectional"))
      (node (ref "XBEE(SERIAL)") (pin "10") (pinfunction "GND_10") (pintype "power_in"))
    )
    (net (code "25") (name "N$29") (class "Default")
      (node (ref "RFID(SPI)") (pin "4") (pinfunction "4_4") (pintype "passive"))
    )
    (net (code "26") (name "Net-(BUT1(A0)-P)") (class "Default")
      (node (ref "BUT1(A0)") (pin "A") (pinfunction "P_A") (pintype "passive"))
      (node (ref "BUT1(A0)") (pin "A'") (pinfunction "P1_A'") (pintype "passive"))
      (node (ref "R22") (pin "2") (pinfunction "2_2") (pintype "passive"))
    )
    (net (code "27") (name "Net-(C13-Pad1)") (class "Default")
      (node (ref "C13") (pin "1") (pinfunction "1_1") (pintype "passive"))
      (node (ref "R8") (pin "1") (pinfunction "1_1") (pintype "passive"))
    )
    (net (code "28") (name "Net-(C14-Pad1)") (class "Default")
      (node (ref "C14") (pin "1") (pinfunction "1_1") (pintype "passive"))
      (node (ref "R10") (pin "1") (pinfunction "1_1") (pintype "passive"))
    )
    (net (code "29") (name "Net-(C15-Pad1)") (class "Default")
      (node (ref "C15") (pin "1") (pinfunction "1_1") (pintype "passive"))
      (node (ref "R11") (pin "1") (pinfunction "1_1") (pintype "passive"))
    )
    (net (code "30") (name "Net-(FET(D7-D5)-Pad2)") (class "Default")
      (node (ref "FET(D7-D5)") (pin "2") (pinfunction "2_2") (pintype "bidirectional"))
      (node (ref "R8") (pin "2") (pinfunction "2_2") (pintype "passive"))
      (node (ref "T1") (pin "2") (pinfunction "D_2") (pintype "passive"))
      (node (ref "T1") (pin "4") (pinfunction "D_4") (pintype "passive"))
    )
    (net (code "31") (name "Net-(FET(D7-D5)-Pad3)") (class "Default")
      (node (ref "FET(D7-D5)") (pin "3") (pinfunction "3_3") (pintype "bidirectional"))
      (node (ref "R10") (pin "2") (pinfunction "2_2") (pintype "passive"))
      (node (ref "T4") (pin "2") (pinfunction "D_2") (pintype "passive"))
      (node (ref "T4") (pin "4") (pinfunction "D_4") (pintype "passive"))
    )
    (net (code "32") (name "Net-(FET(D7-D5)-Pad4)") (class "Default")
      (node (ref "FET(D7-D5)") (pin "4") (pinfunction "4_4") (pintype "bidirectional"))
      (node (ref "R11") (pin "2") (pinfunction "2_2") (pintype "passive"))
      (node (ref "T2") (pin "2") (pinfunction "D_2") (pintype "passive"))
      (node (ref "T2") (pin "4") (pinfunction "D_4") (pintype "passive"))
    )
    (net (code "33") (name "Net-(HALL(A2)-OUT)") (class "Default")
      (node (ref "HALL(A2)") (pin "2") (pinfunction "OUT_2") (pintype "output"))
      (node (ref "S4") (pin "2") (pinfunction "2_2") (pintype "passive"))
    )
    (net (code "34") (name "Net-(IC1-O1)") (class "Default")
      (node (ref "IC1") (pin "17") (pinfunction "O2_17") (pintype "open_collector"))
      (node (ref "IC1") (pin "18") (pinfunction "O1_18") (pintype "open_collector"))
      (node (ref "STEPPER1") (pin "2") (pinfunction "2_2") (pintype "passive"))
    )
    (net (code "35") (name "Net-(IC1-O3)") (class "Default")
      (node (ref "IC1") (pin "15") (pinfunction "O4_15") (pintype "open_collector"))
      (node (ref "IC1") (pin "16") (pinfunction "O3_16") (pintype "open_collector"))
      (node (ref "STEPPER1") (pin "3") (pinfunction "3_3") (pintype "passive"))
    )
    (net (code "36") (name "Net-(IC1-O5)") (class "Default")
      (node (ref "IC1") (pin "13") (pinfunction "O6_13") (pintype "open_collector"))
      (node (ref "IC1") (pin "14") (pinfunction "O5_14") (pintype "open_collector"))
      (node (ref "STEPPER1") (pin "4") (pinfunction "4_4") (pintype "passive"))
    )
    (net (code "37") (name "Net-(IC1-O7)") (class "Default")
      (node (ref "IC1") (pin "11") (pinfunction "O8_11") (pintype "open_collector"))
      (node (ref "IC1") (pin "12") (pinfunction "O7_12") (pintype "open_collector"))
      (node (ref "STEPPER1") (pin "5") (pinfunction "5_5") (pintype "passive"))
    )
    (net (code "38") (name "Net-(IC2-O1)") (class "Default")
      (node (ref "IC2") (pin "17") (pinfunction "O2_17") (pintype "open_collector"))
      (node (ref "IC2") (pin "18") (pinfunction "O1_18") (pintype "open_collector"))
      (node (ref "STEPPER2") (pin "2") (pinfunction "2_2") (pintype "passive"))
    )
    (net (code "39") (name "Net-(IC2-O3)") (class "Default")
      (node (ref "IC2") (pin "15") (pinfunction "O4_15") (pintype "open_collector"))
      (node (ref "IC2") (pin "16") (pinfunction "O3_16") (pintype "open_collector"))
      (node (ref "STEPPER2") (pin "3") (pinfunction "3_3") (pintype "passive"))
    )
    (net (code "40") (name "Net-(IC2-O5)") (class "Default")
      (node (ref "IC2") (pin "13") (pinfunction "O6_13") (pintype "open_collector"))
      (node (ref "IC2") (pin "14") (pinfunction "O5_14") (pintype "open_collector"))
      (node (ref "STEPPER2") (pin "4") (pinfunction "4_4") (pintype "passive"))
    )
    (net (code "41") (name "Net-(IC2-O7)") (class "Default")
      (node (ref "IC2") (pin "11") (pinfunction "O8_11") (pintype "open_collector"))
      (node (ref "IC2") (pin "12") (pinfunction "O7_12") (pintype "open_collector"))
      (node (ref "STEPPER2") (pin "5") (pinfunction "5_5") (pintype "passive"))
    )
    (net (code "42") (name "Net-(LED1-PadA)") (class "Default")
      (node (ref "LED1") (pin "A") (pinfunction "A_A") (pintype "passive"))
      (node (ref "R16") (pin "1") (pinfunction "1_1") (pintype "passive"))
    )
    (net (code "43") (name "Net-(LED2-PadA)") (class "Default")
      (node (ref "LED2") (pin "A") (pinfunction "A_A") (pintype "passive"))
      (node (ref "R17") (pin "1") (pinfunction "1_1") (pintype "passive"))
    )
    (net (code "44") (name "Net-(LED3-PadA)") (class "Default")
      (node (ref "LED3") (pin "A") (pinfunction "A_A") (pintype "passive"))
      (node (ref "R18") (pin "1") (pinfunction "1_1") (pintype "passive"))
    )
    (net (code "45") (name "Net-(LED4-PadA)") (class "Default")
      (node (ref "LED4") (pin "A") (pinfunction "A_A") (pintype "passive"))
      (node (ref "R19") (pin "1") (pinfunction "1_1") (pintype "passive"))
    )
    (net (code "46") (name "Net-(POT(A0)-S)") (class "Default")
      (node (ref "POT(A0)") (pin "2") (pinfunction "S_2") (pintype "passive"))
      (node (ref "S6") (pin "1") (pinfunction "1_1") (pintype "passive"))
    )
    (net (code "47") (name "Net-(PWR_LED-PadC)") (class "Default")
      (node (ref "PWR_LED") (pin "C") (pinfunction "C_C") (pintype "passive"))
      (node (ref "R5") (pin "2") (pinfunction "2_2") (pintype "passive"))
    )
    (net (code "48") (name "Net-(R9-Pad2)") (class "Default")
      (node (ref "R9") (pin "2") (pinfunction "2_2") (pintype "passive"))
      (node (ref "RTC(A1)") (pin "2") (pinfunction "2_2") (pintype "passive"))
      (node (ref "S5") (pin "2") (pinfunction "2_2") (pintype "passive"))
    )
    (net (code "49") (name "Net-(R20-Pad2)") (class "Default")
      (node (ref "R20") (pin "2") (pinfunction "2_2") (pintype "passive"))
      (node (ref "S1") (pin "1") (pinfunction "1_1") (pintype "passive"))
    )
    (net (code "50") (name "Net-(R21-Pad2)") (class "Default")
      (node (ref "R21") (pin "2") (pinfunction "2_2") (pintype "passive"))
      (node (ref "S2") (pin "1") (pinfunction "1_1") (pintype "passive"))
    )
    (net (code "51") (name "Net-(SJ1-Pad3)") (class "Default")
      (node (ref "SJ1") (pin "3") (pinfunction "3_3") (pintype "passive"))
      (node (ref "U$5") (pin "SCL") (pinfunction "SCL_SCL") (pintype "bidirectional"))
    )
    (net (code "52") (name "Net-(SJ2-Pad3)") (class "Default")
      (node (ref "SJ2") (pin "3") (pinfunction "3_3") (pintype "passive"))
      (node (ref "U$5") (pin "SDA") (pinfunction "SDA_SDA") (pintype "bidirectional"))
    )
    (net (code "53") (name "Net-(SPK-+)") (class "Default")
      (node (ref "S7") (pin "2") (pinfunction "2_2") (pintype "passive"))
      (node (ref "SPK") (pin "-") (pinfunction "+_-") (pintype "passive"))
    )
    (net (code "54") (name "Net-(TEMP(0X48/49)-A0)") (class "Default")
      (node (ref "R1") (pin "1") (pinfunction "1_1") (pintype "passive"))
      (node (ref "S3") (pin "2") (pinfunction "2_2") (pintype "passive"))
      (node (ref "TEMP(0X48/49)") (pin "7") (pinfunction "A0_7") (pintype "bidirectional"))
    )
    (net (code "55") (name "Net-(U$4-P$2)") (class "Default")
      (node (ref "C10") (pin "1") (pinfunction "1_1") (pintype "passive"))
      (node (ref "U$4") (pin "2") (pinfunction "P$2_2") (pintype "bidirectional"))
    )
    (net (code "56") (name "Net-(U$4-P$3)") (class "Default")
      (node (ref "C10") (pin "2") (pinfunction "2_2") (pintype "passive"))
      (node (ref "U$4") (pin "3") (pinfunction "P$3_3") (pintype "bidirectional"))
    )
    (net (code "57") (name "Net-(U$4-P$4)") (class "Default")
      (node (ref "C18") (pin "1") (pinfunction "1_1") (pintype "passive"))
      (node (ref "U$4") (pin "4") (pinfunction "P$4_4") (pintype "bidirectional"))
    )
    (net (code "58") (name "Net-(U$4-P$5)") (class "Default")
      (node (ref "C18") (pin "2") (pinfunction "2_2") (pintype "passive"))
      (node (ref "U$4") (pin "5") (pinfunction "P$5_5") (pintype "bidirectional"))
    )
    (net (code "59") (name "Net-(U$4-P$26)") (class "Default")
      (node (ref "R4") (pin "2") (pinfunction "2_2") (pintype "passive"))
      (node (ref "U$4") (pin "26") (pinfunction "P$26_26") (pintype "bidirectional"))
    )
    (net (code "60") (name "Net-(U$4-P$27)") (class "Default")
      (node (ref "C12") (pin "1") (pinfunction "1_1") (pintype "passive"))
      (node (ref "U$4") (pin "27") (pinfunction "P$27_27") (pintype "bidirectional"))
    )
    (net (code "61") (name "Net-(U$4-P$28)") (class "Default")
      (node (ref "C19") (pin "1") (pinfunction "1_1") (pintype "passive"))
      (node (ref "U$4") (pin "28") (pinfunction "P$28_28") (pintype "bidirectional"))
    )
    (net (code "62") (name "OUT1") (class "Default")
      (node (ref "D1") (pin "A") (pinfunction "A_A") (pintype "passive"))
      (node (ref "D2") (pin "C") (pinfunction "C_C") (pintype "passive"))
      (node (ref "DCMOT(D7-D2)") (pin "4") (pinfunction "4_4") (pintype "bidirectional"))
      (node (ref "U2") (pin "P$4") (pinfunction "OUT1_P$4") (pintype "bidirectional"))
    )
    (net (code "63") (name "OUT2") (class "Default")
      (node (ref "D3") (pin "A") (pinfunction "A_A") (pintype "passive"))
      (node (ref "D4") (pin "C") (pinfunction "C_C") (pintype "passive"))
      (node (ref "DCMOT(D7-D2)") (pin "3") (pinfunction "3_3") (pintype "bidirectional"))
      (node (ref "U2") (pin "P$5") (pinfunction "OUT2_P$5") (pintype "bidirectional"))
    )
    (net (code "64") (name "OUT3") (class "Default")
      (node (ref "D7") (pin "A") (pinfunction "A_A") (pintype "passive"))
      (node (ref "D8") (pin "C") (pinfunction "C_C") (pintype "passive"))
      (node (ref "DCMOT(D7-D2)") (pin "1") (pinfunction "1_1") (pintype "bidirectional"))
      (node (ref "U2") (pin "P$17") (pinfunction "OUT4_P$17") (pintype "bidirectional"))
    )
    (net (code "65") (name "OUT4") (class "Default")
      (node (ref "D5") (pin "A") (pinfunction "A_A") (pintype "passive"))
      (node (ref "D6") (pin "C") (pinfunction "C_C") (pintype "passive"))
      (node (ref "DCMOT(D7-D2)") (pin "2") (pinfunction "2_2") (pintype "bidirectional"))
      (node (ref "U2") (pin "P$16") (pinfunction "OUT3_P$16") (pintype "bidirectional"))
    )
    (net (code "66") (name "PTB18") (class "Default")
      (node (ref "D0-7") (pin "1") (pinfunction "1_1") (pintype "passive"))
    )
    (net (code "67") (name "PTB19") (class "Default")
      (node (ref "D0-7") (pin "2") (pinfunction "2_2") (pintype "passive"))
    )
    (net (code "68") (name "PTC0") (class "Default")
      (node (ref "D0-7") (pin "6") (pinfunction "6_6") (pintype "passive"))
      (node (ref "IC2") (pin "5") (pinfunction "I5_5") (pintype "input"))
      (node (ref "IC2") (pin "6") (pinfunction "I6_6") (pintype "input"))
    )
    (net (code "69") (name "PTC1") (class "Default")
      (node (ref "D0-7") (pin "3") (pinfunction "3_3") (pintype "passive"))
    )
    (net (code "70") (name "PTC5") (class "Default")
      (node (ref "D0-7") (pin "8") (pinfunction "8_8") (pintype "passive"))
      (node (ref "IC2") (pin "1") (pinfunction "I1_1") (pintype "input"))
      (node (ref "IC2") (pin "2") (pinfunction "I2_2") (pintype "input"))
    )
    (net (code "71") (name "PTC7") (class "Default")
      (node (ref "D0-7") (pin "7") (pinfunction "7_7") (pintype "passive"))
      (node (ref "IC2") (pin "3") (pinfunction "I3_3") (pintype "input"))
      (node (ref "IC2") (pin "4") (pinfunction "I4_4") (pintype "input"))
    )
    (net (code "72") (name "PTC8") (class "Default")
      (node (ref "D0-7") (pin "4") (pinfunction "4_4") (pintype "passive"))
    )
    (net (code "73") (name "PTC9") (class "Default")
      (node (ref "D0-7") (pin "5") (pinfunction "5_5") (pintype "passive"))
      (node (ref "IC2") (pin "7") (pinfunction "I7_7") (pintype "input"))
      (node (ref "IC2") (pin "8") (pinfunction "I8_8") (pintype "input"))
    )
    (net (code "74") (name "RX") (class "Default")
      (node (ref "BLUETOOTH") (pin "3") (pinfunction "3_3") (pintype "passive"))
      (node (ref "ESP8266") (pin "8") (pinfunction "8_8") (pintype "passive"))
      (node (ref "SERIAL") (pin "4") (pinfunction "4_4") (pintype "bidirectional"))
      (node (ref "SJ4") (pin "2") (pinfunction "2_2") (pintype "passive"))
      (node (ref "XBEE(SERIAL)") (pin "2") (pinfunction "DOUT_2") (pintype "output"))
    )
    (net (code "75") (name "SCL") (class "Default")
      (node (ref "I2C-1") (pin "4") (pinfunction "4_4") (pintype "bidirectional"))
      (node (ref "I2C-2") (pin "4") (pinfunction "4_4") (pintype "bidirectional"))
      (node (ref "J5") (pin "1") (pinfunction "1_1") (pintype "bidirectional"))
      (node (ref "R21") (pin "1") (pinfunction "1_1") (pintype "passive"))
      (node (ref "SJ1") (pin "2") (pinfunction "2_2") (pintype "passive"))
      (node (ref "TEMP(0X48/49)") (pin "2") (pinfunction "SCL_2") (pintype "bidirectional"))
      (node (ref "U$4") (pin "18") (pinfunction "P$18_18") (pintype "bidirectional"))
      (node (ref "XBEE(SERIAL)") (pin "19") (pinfunction "AD1/DIO1_19") (pintype "bidirectional"))
    )
    (net (code "76") (name "SDA") (class "Default")
      (node (ref "I2C-1") (pin "3") (pinfunction "3_3") (pintype "bidirectional"))
      (node (ref "I2C-2") (pin "3") (pinfunction "3_3") (pintype "bidirectional"))
      (node (ref "J5") (pin "2") (pinfunction "2_2") (pintype "bidirectional"))
      (node (ref "R20") (pin "1") (pinfunction "1_1") (pintype "passive"))
      (node (ref "SJ2") (pin "2") (pinfunction "2_2") (pintype "passive"))
      (node (ref "TEMP(0X48/49)") (pin "1") (pinfunction "SDA_1") (pintype "bidirectional"))
      (node (ref "U$4") (pin "19") (pinfunction "P$19_19") (pintype "bidirectional"))
      (node (ref "U$4") (pin "20") (pinfunction "P$20_20") (pintype "bidirectional"))
      (node (ref "XBEE(SERIAL)") (pin "20") (pinfunction "AD0/DIO0_20") (pintype "bidirectional"))
    )
    (net (code "77") (name "TX") (class "Default")
      (node (ref "BLUETOOTH") (pin "2") (pinfunction "2_2") (pintype "passive"))
      (node (ref "ESP8266") (pin "1") (pinfunction "1_1") (pintype "passive"))
      (node (ref "SERIAL") (pin "3") (pinfunction "3_3") (pintype "bidirectional"))
      (node (ref "SJ3") (pin "2") (pinfunction "2_2") (pintype "passive"))
      (node (ref "XBEE(SERIAL)") (pin "3") (pinfunction "DIN_3") (pintype "input"))
    )
    (net (code "78") (name "VIN") (class "Default")
      (node (ref "U$5") (pin "VIN") (pinfunction "VIN_VIN") (pintype "power_in"))
    )
    (net (code "79") (name "unconnected-(ESP8266-Pad3)") (class "Default")
      (node (ref "ESP8266") (pin "3") (pinfunction "3_3") (pintype "passive"))
    )
    (net (code "80") (name "unconnected-(ESP8266-Pad5)") (class "Default")
      (node (ref "ESP8266") (pin "5") (pinfunction "5_5") (pintype "passive"))
    )
    (net (code "81") (name "unconnected-(TEMP(0X48/49)-ALERT-Pad3)") (class "Default")
      (node (ref "TEMP(0X48/49)") (pin "3") (pinfunction "ALERT_3") (pintype "bidirectional"))
    )
    (net (code "82") (name "unconnected-(U$4-P$1-Pad1)") (class "Default")
      (node (ref "U$4") (pin "1") (pinfunction "P$1_1") (pintype "bidirectional"))
    )
    (net (code "83") (name "unconnected-(U$4-P$7-Pad7)") (class "Default")
      (node (ref "U$4") (pin "7") (pinfunction "P$7_7") (pintype "bidirectional"))
    )
    (net (code "84") (name "unconnected-(U$4-P$30-Pad30)") (class "Default")
      (node (ref "U$4") (pin "30") (pinfunction "P$30_30") (pintype "bidirectional"))
    )
    (net (code "85") (name "unconnected-(U$5-PadAREF)") (class "Default")
      (node (ref "U$5") (pin "AREF") (pinfunction "AREF_AREF") (pintype "bidirectional"))
    )
    (net (code "86") (name "unconnected-(U$5-PadIOREF)") (class "Default")
      (node (ref "U$5") (pin "IOREF") (pinfunction "IOREF_IOREF") (pintype "output"))
    )
    (net (code "87") (name "unconnected-(U$5-PadRESERVED)") (class "Default")
      (node (ref "U$5") (pin "RESERVED") (pinfunction "RESERVED_RESERVED") (pintype "no_connect"))
    )
    (net (code "88") (name "unconnected-(U2-NC-PadP$3)") (class "Default")
      (node (ref "U2") (pin "P$3") (pinfunction "NC_P$3") (pintype "bidirectional"))
    )
    (net (code "89") (name "unconnected-(U2-NC-PadP$18)") (class "Default")
      (node (ref "U2") (pin "P$18") (pinfunction "NC_P$18") (pintype "bidirectional"))
    )
    (net (code "90") (name "unconnected-(XBEE(SERIAL)-AD2{slash}DIO2-Pad18)") (class "Default")
      (node (ref "XBEE(SERIAL)") (pin "18") (pinfunction "AD2/DIO2_18") (pintype "bidirectional"))
    )
    (net (code "91") (name "unconnected-(XBEE(SERIAL)-AD3{slash}DIO3-Pad17)") (class "Default")
      (node (ref "XBEE(SERIAL)") (pin "17") (pinfunction "AD3/DIO3_17") (pintype "bidirectional"))
    )
    (net (code "92") (name "unconnected-(XBEE(SERIAL)-AD4{slash}DIO4-Pad11)") (class "Default")
      (node (ref "XBEE(SERIAL)") (pin "11") (pinfunction "AD4/DIO4_11") (pintype "bidirectional"))
    )
    (net (code "93") (name "unconnected-(XBEE(SERIAL)-ASC{slash}AD5{slash}DIO5-Pad15)") (class "Default")
      (node (ref "XBEE(SERIAL)") (pin "15") (pinfunction "ASC/AD5/DIO5_15") (pintype "bidirectional"))
    )
    (net (code "94") (name "unconnected-(XBEE(SERIAL)-CTS{slash}DIO7-Pad12)") (class "Default")
      (node (ref "XBEE(SERIAL)") (pin "12") (pinfunction "CTS/DIO7_12") (pintype "bidirectional"))
    )
    (net (code "95") (name "unconnected-(XBEE(SERIAL)-DO8-Pad4)") (class "Default")
      (node (ref "XBEE(SERIAL)") (pin "4") (pinfunction "DO8_4") (pintype "output"))
    )
    (net (code "96") (name "unconnected-(XBEE(SERIAL)-DTR{slash}DI8-Pad9)") (class "Default")
      (node (ref "XBEE(SERIAL)") (pin "9") (pinfunction "DTR/DI8_9") (pintype "input"))
    )
    (net (code "97") (name "unconnected-(XBEE(SERIAL)-ON{slash}SLEEP-Pad13)") (class "Default")
      (node (ref "XBEE(SERIAL)") (pin "13") (pinfunction "ON/SLEEP_13") (pintype "output"))
    )
    (net (code "98") (name "unconnected-(XBEE(SERIAL)-PWM0{slash}RSSI-Pad6)") (class "Default")
      (node (ref "XBEE(SERIAL)") (pin "6") (pinfunction "PWM0/RSSI_6") (pintype "output"))
    )
    (net (code "99") (name "unconnected-(XBEE(SERIAL)-PWM1-Pad7)") (class "Default")
      (node (ref "XBEE(SERIAL)") (pin "7") (pinfunction "PWM1_7") (pintype "output"))
    )
    (net (code "100") (name "unconnected-(XBEE(SERIAL)-RESERVED-Pad8)") (class "Default")
      (node (ref "XBEE(SERIAL)") (pin "8") (pinfunction "RESERVED_8") (pintype "no_connect"))
    )
    (net (code "101") (name "unconnected-(XBEE(SERIAL)-RESET-Pad5)") (class "Default")
      (node (ref "XBEE(SERIAL)") (pin "5") (pinfunction "RESET_5") (pintype "input"))
    )
    (net (code "102") (name "unconnected-(XBEE(SERIAL)-RTS{slash}AD6{slash}DIO6-Pad16)") (class "Default")
      (node (ref "XBEE(SERIAL)") (pin "16") (pinfunction "RTS/AD6/DIO6_16") (pintype "bidirectional"))
    )
    (net (code "103") (name "unconnected-(XBEE(SERIAL)-VREF-Pad14)") (class "Default")
      (node (ref "XBEE(SERIAL)") (pin "14") (pinfunction "VREF_14") (pintype "input"))
    )
    (net (code "104") (name "{slash}RST") (class "Default")
      (node (ref "RESET") (pin "B") (pinfunction "S_B") (pintype "passive"))
      (node (ref "RESET") (pin "B'") (pinfunction "S1_B'") (pintype "passive"))
      (node (ref "U$5") (pin "RESET") (pinfunction "/RESET_RESET") (pintype "bidirectional"))
    )
  )
)
